# Domino_LED_Overlap_No_Teardrop.net
KiCad netlist of a schematic drawn in EAGLE
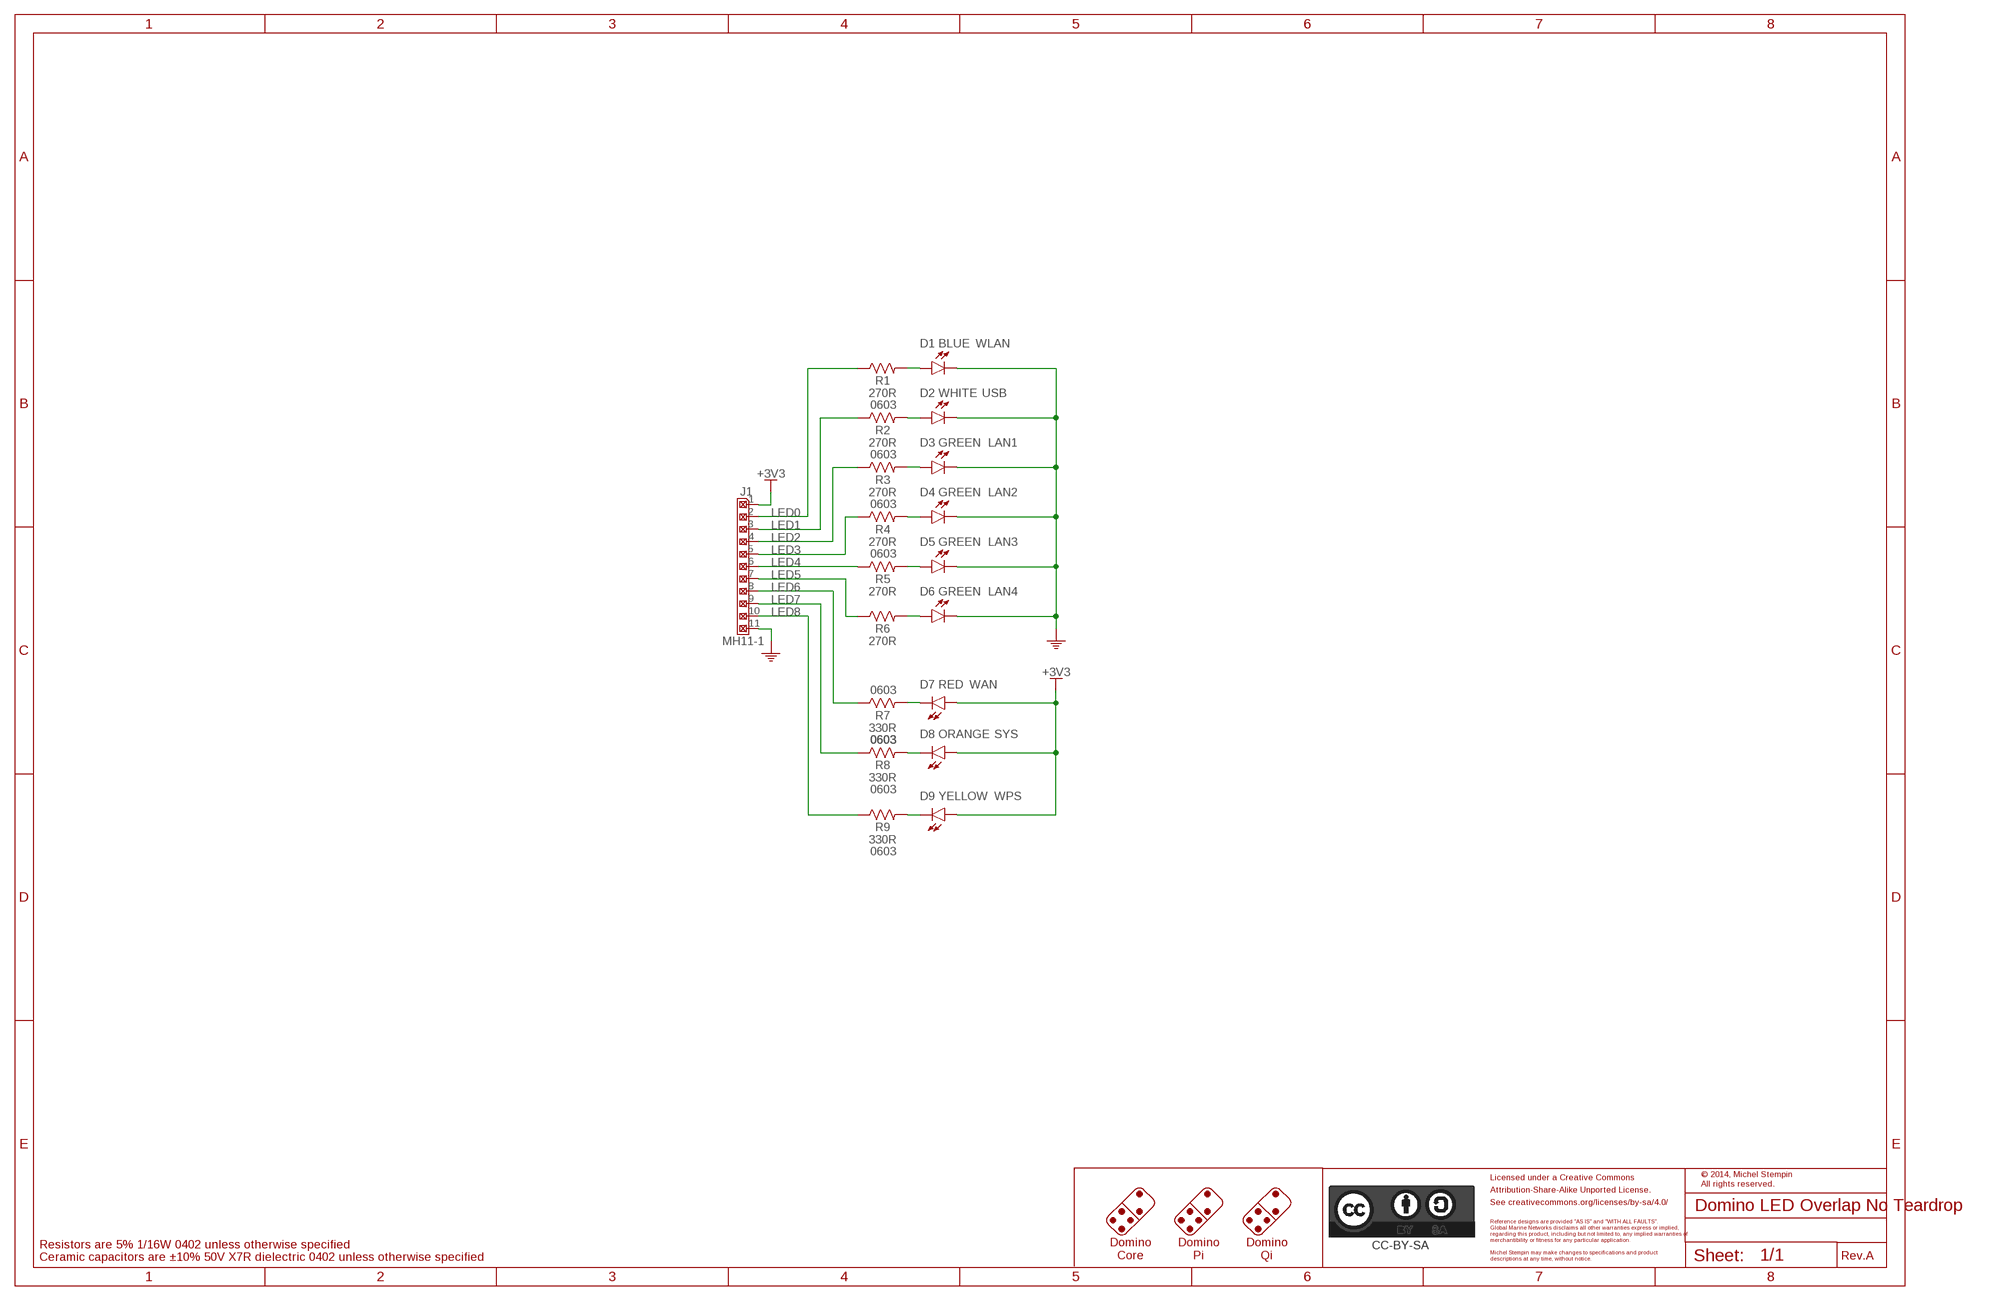
[diagram p0: schematic, sheet 1]

(export (version "E")
  (design (tool "Eeschema 10.0.6"))
  (components
    (comp (ref "CC-BY-SA1")
      (value "CC-BY-SA_LOGO")
      (footprint "eagle-import:CC-BY-SA_LOGO")
      (libsource (lib "eagle-import") (part "CC-BY-SA_LOGO"))
    )
    (comp (ref "D1")
      (value "BLUE")
      (footprint "eagle-import:LED0603")
      (fields (field (name "PARTNO") "LED0603-BLUE"))
      (libsource (lib "eagle-import") (part "LED_0603"))
    )
    (comp (ref "D2")
      (value "WHITE")
      (footprint "eagle-import:LED0603")
      (fields (field (name "PARTNO") "LED0603-WHITE"))
      (libsource (lib "eagle-import") (part "LED_0603"))
    )
    (comp (ref "D3")
      (value "GREEN")
      (footprint "eagle-import:LED0603")
      (fields (field (name "PARTNO") "LED0603-GREEN"))
      (libsource (lib "eagle-import") (part "LED_0603"))
    )
    (comp (ref "D4")
      (value "GREEN")
      (footprint "eagle-import:LED0603")
      (fields (field (name "PARTNO") "LED0603-GREEN"))
      (libsource (lib "eagle-import") (part "LED_0603"))
    )
    (comp (ref "D5")
      (value "GREEN")
      (footprint "eagle-import:LED0603")
      (fields (field (name "PARTNO") "LED0603-GREEN"))
      (libsource (lib "eagle-import") (part "LED_0603"))
    )
    (comp (ref "D6")
      (value "GREEN")
      (footprint "eagle-import:LED0603")
      (fields (field (name "PARTNO") "LED0603-GREEN"))
      (libsource (lib "eagle-import") (part "LED_0603"))
    )
    (comp (ref "D7")
      (value "RED")
      (footprint "eagle-import:LED0603")
      (fields (field (name "PARTNO") "LED0603-RED"))
      (libsource (lib "eagle-import") (part "LED_0603"))
    )
    (comp (ref "D8")
      (value "ORANGE")
      (footprint "eagle-import:LED0603")
      (fields (field (name "PARTNO") "LED0603-ORANGE"))
      (libsource (lib "eagle-import") (part "LED_0603"))
    )
    (comp (ref "D9")
      (value "YELLOW")
      (footprint "eagle-import:LED0603")
      (fields (field (name "PARTNO") "LED0603-YELLOW"))
      (libsource (lib "eagle-import") (part "LED_0603"))
    )
    (comp (ref "J1")
      (value "MH11-1")
      (footprint "eagle-import:MH11-1-0.1")
      (fields (field (name "PARTNO") "MH11-1-0.1"))
      (libsource (lib "eagle-import") (part "MH11-1"))
    )
    (comp (ref "R1")
      (value "270R")
      (footprint "eagle-import:R0603")
      (fields (field (name "SIZE") "0603") (field (name "PARTNO") "R0603_270R_5%_125mW"))
      (libsource (lib "eagle-import") (part "RES_0603"))
    )
    (comp (ref "R2")
      (value "270R")
      (footprint "eagle-import:R0603")
      (fields (field (name "SIZE") "0603") (field (name "PARTNO") "R0603_270R_5%_125mW"))
      (libsource (lib "eagle-import") (part "RES_0603"))
    )
    (comp (ref "R3")
      (value "270R")
      (footprint "eagle-import:R0603")
      (fields (field (name "SIZE") "0603") (field (name "PARTNO") "R0603_270R_5%_125mW"))
      (libsource (lib "eagle-import") (part "RES_0603"))
    )
    (comp (ref "R4")
      (value "270R")
      (footprint "eagle-import:R0603")
      (fields (field (name "SIZE") "0603") (field (name "PARTNO") "R0603_270R_5%_125mW"))
      (libsource (lib "eagle-import") (part "RES_0603"))
    )
    (comp (ref "R5")
      (value "270R")
      (footprint "eagle-import:R0603")
      (fields (field (name "SIZE") "0603") (field (name "PARTNO") "R0603_270R_5%_125mW"))
      (libsource (lib "eagle-import") (part "RES_0603"))
    )
    (comp (ref "R6")
      (value "270R")
      (footprint "eagle-import:R0603")
      (fields (field (name "SIZE") "0603") (field (name "PARTNO") "R0603_270R_5%_125mW"))
      (libsource (lib "eagle-import") (part "RES_0603"))
    )
    (comp (ref "R7")
      (value "330R")
      (footprint "eagle-import:R0603")
      (fields (field (name "SIZE") "0603") (field (name "PARTNO") "R0603_330R_5%_125mW"))
      (libsource (lib "eagle-import") (part "RES_0603"))
    )
    (comp (ref "R8")
      (value "330R")
      (footprint "eagle-import:R0603")
      (fields (field (name "SIZE") "0603") (field (name "PARTNO") "R0603_330R_5%_125mW"))
      (libsource (lib "eagle-import") (part "RES_0603"))
    )
    (comp (ref "R9")
      (value "330R")
      (footprint "eagle-import:R0603")
      (fields (field (name "SIZE") "0603") (field (name "PARTNO") "R0603_330R_5%_125mW"))
      (libsource (lib "eagle-import") (part "RES_0603"))
    )
  )
  (nets
    (net (code "1") (name "+3V3") (class "Default")
      (node (ref "D7") (pin "2") (pinfunction "A_2") (pintype "passive"))
      (node (ref "D8") (pin "2") (pinfunction "A_2") (pintype "passive"))
      (node (ref "D9") (pin "2") (pinfunction "A_2") (pintype "passive"))
      (node (ref "J1") (pin "1") (pinfunction "1_1") (pintype "passive"))
    )
    (net (code "2") (name "/LED0") (class "Default")
      (node (ref "J1") (pin "2") (pinfunction "2_2") (pintype "passive"))
      (node (ref "R1") (pin "1") (pinfunction "1_1") (pintype "passive"))
    )
    (net (code "3") (name "/LED1") (class "Default")
      (node (ref "J1") (pin "3") (pinfunction "3_3") (pintype "passive"))
      (node (ref "R2") (pin "1") (pinfunction "1_1") (pintype "passive"))
    )
    (net (code "4") (name "/LED2") (class "Default")
      (node (ref "J1") (pin "4") (pinfunction "4_4") (pintype "passive"))
      (node (ref "R3") (pin "1") (pinfunction "1_1") (pintype "passive"))
    )
    (net (code "5") (name "/LED3") (class "Default")
      (node (ref "J1") (pin "5") (pinfunction "5_5") (pintype "passive"))
      (node (ref "R4") (pin "1") (pinfunction "1_1") (pintype "passive"))
    )
    (net (code "6") (name "/LED4") (class "Default")
      (node (ref "J1") (pin "6") (pinfunction "6_6") (pintype "passive"))
      (node (ref "R5") (pin "1") (pinfunction "1_1") (pintype "passive"))
    )
    (net (code "7") (name "/LED5") (class "Default")
      (node (ref "J1") (pin "7") (pinfunction "7_7") (pintype "passive"))
      (node (ref "R6") (pin "1") (pinfunction "1_1") (pintype "passive"))
    )
    (net (code "8") (name "/LED6") (class "Default")
      (node (ref "J1") (pin "8") (pinfunction "8_8") (pintype "passive"))
      (node (ref "R7") (pin "1") (pinfunction "1_1") (pintype "passive"))
    )
    (net (code "9") (name "/LED7") (class "Default")
      (node (ref "J1") (pin "9") (pinfunction "9_9") (pintype "passive"))
      (node (ref "R8") (pin "1") (pinfunction "1_1") (pintype "passive"))
    )
    (net (code "10") (name "/LED8") (class "Default")
      (node (ref "J1") (pin "10") (pinfunction "10_10") (pintype "passive"))
      (node (ref "R9") (pin "1") (pinfunction "1_1") (pintype "passive"))
    )
    (net (code "11") (name "GND") (class "Default")
      (node (ref "D1") (pin "1") (pinfunction "C_1") (pintype "passive"))
      (node (ref "D2") (pin "1") (pinfunction "C_1") (pintype "passive"))
      (node (ref "D3") (pin "1") (pinfunction "C_1") (pintype "passive"))
      (node (ref "D4") (pin "1") (pinfunction "C_1") (pintype "passive"))
      (node (ref "D5") (pin "1") (pinfunction "C_1") (pintype "passive"))
      (node (ref "D6") (pin "1") (pinfunction "C_1") (pintype "passive"))
      (node (ref "J1") (pin "11") (pinfunction "11_11") (pintype "passive"))
    )
    (net (code "12") (name "Net-(D1-A)") (class "Default")
      (node (ref "D1") (pin "2") (pinfunction "A_2") (pintype "passive"))
      (node (ref "R1") (pin "2") (pinfunction "2_2") (pintype "passive"))
    )
    (net (code "13") (name "Net-(D2-A)") (class "Default")
      (node (ref "D2") (pin "2") (pinfunction "A_2") (pintype "passive"))
      (node (ref "R2") (pin "2") (pinfunction "2_2") (pintype "passive"))
    )
    (net (code "14") (name "Net-(D3-A)") (class "Default")
      (node (ref "D3") (pin "2") (pinfunction "A_2") (pintype "passive"))
      (node (ref "R3") (pin "2") (pinfunction "2_2") (pintype "passive"))
    )
    (net (code "15") (name "Net-(D4-A)") (class "Default")
      (node (ref "D4") (pin "2") (pinfunction "A_2") (pintype "passive"))
      (node (ref "R4") (pin "2") (pinfunction "2_2") (pintype "passive"))
    )
    (net (code "16") (name "Net-(D5-A)") (class "Default")
      (node (ref "D5") (pin "2") (pinfunction "A_2") (pintype "passive"))
      (node (ref "R5") (pin "2") (pinfunction "2_2") (pintype "passive"))
    )
    (net (code "17") (name "Net-(D6-A)") (class "Default")
      (node (ref "D6") (pin "2") (pinfunction "A_2") (pintype "passive"))
      (node (ref "R6") (pin "2") (pinfunction "2_2") (pintype "passive"))
    )
    (net (code "18") (name "Net-(D7-C)") (class "Default")
      (node (ref "D7") (pin "1") (pinfunction "C_1") (pintype "passive"))
      (node (ref "R7") (pin "2") (pinfunction "2_2") (pintype "passive"))
    )
    (net (code "19") (name "Net-(D8-C)") (class "Default")
      (node (ref "D8") (pin "1") (pinfunction "C_1") (pintype "passive"))
      (node (ref "R8") (pin "2") (pinfunction "2_2") (pintype "passive"))
    )
    (net (code "20") (name "Net-(D9-C)") (class "Default")
      (node (ref "D9") (pin "1") (pinfunction "C_1") (pintype "passive"))
      (node (ref "R9") (pin "2") (pinfunction "2_2") (pintype "passive"))
    )
  )
)
